# RTC.net
KiCad netlist of a schematic drawn in Altium Designer
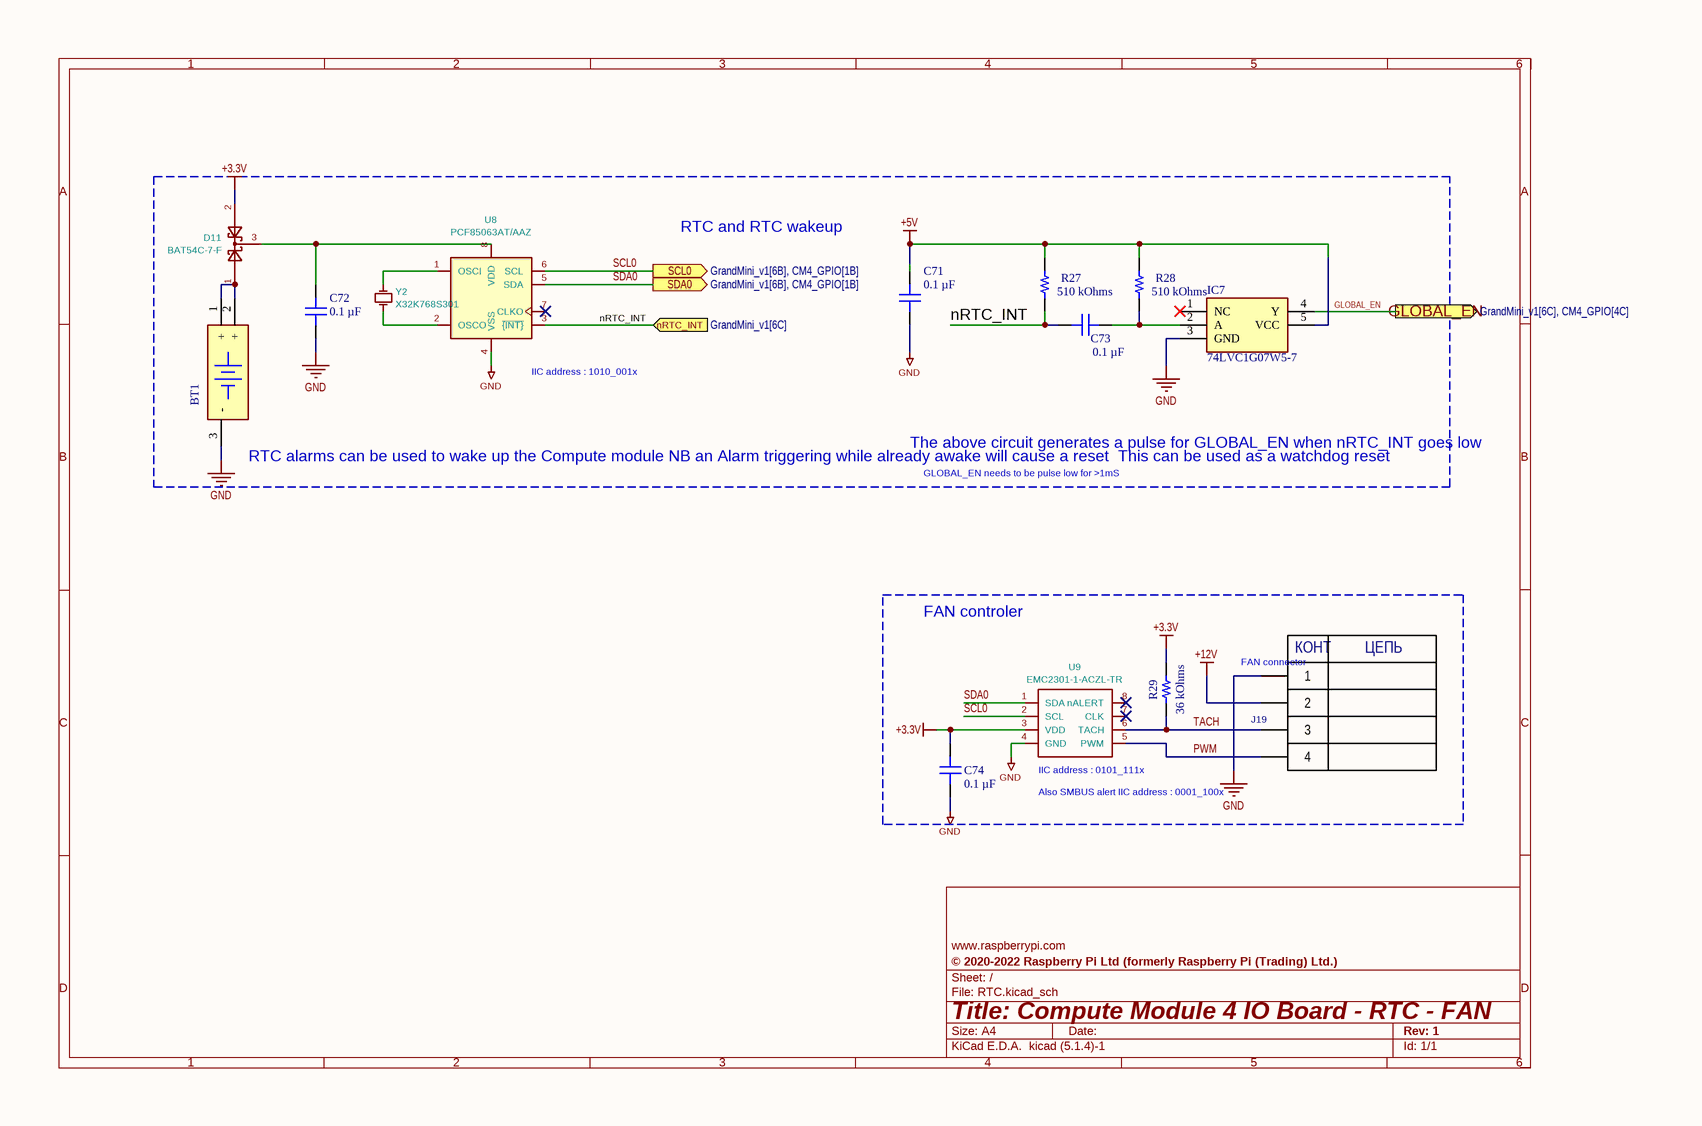
[diagram p0: RTC.SchDoc]

(export (version "E")
  (design (tool "Eeschema 10.0.6"))
  (components
    (comp (ref "BT1")
      (value "CR2032 Holder")
      (footprint "SamacSys:KLS5CR203204")
      (description "Battery Holder, Vertical, CR2032")
      (fields (field (name "MANUFACTURER_PART_NUMBER") "KLS5-CR2032-04"))
      (libsource (lib "SamacSys") (part "KLS5-CR2032-04"))
    )
    (comp (ref "C71")
      (value "0.1 µF")
      (footprint "CAP 0603_1608")
      (description "CAP CER 0.1UF 50V X7R 0603")
      (fields (field (name "PART NUMBER") "CC0603KRX7R9BB104") (field (name "MANUFACTURER") "Yageo"))
      (libsource (lib "Celestial Altium Library - altium_library") (part "Capacitor"))
    )
    (comp (ref "C72")
      (value "0.1 µF")
      (footprint "CAP 0603_1608")
      (description "CAP CER 0.1UF 50V X7R 0603")
      (fields (field (name "PART NUMBER") "CC0603KRX7R9BB104") (field (name "MANUFACTURER") "Yageo"))
      (libsource (lib "Celestial Altium Library - altium_library") (part "Capacitor"))
    )
    (comp (ref "C73")
      (value "0.1 µF")
      (footprint "CAP 0603_1608")
      (description "CAP CER 0.1UF 50V X7R 0603")
      (fields (field (name "PART NUMBER") "CC0603KRX7R9BB104") (field (name "MANUFACTURER") "Yageo"))
      (libsource (lib "Celestial Altium Library - altium_library") (part "Capacitor"))
    )
    (comp (ref "C74")
      (value "0.1 µF")
      (footprint "CAP 0603_1608")
      (description "CAP CER 0.1UF 50V X7R 0603")
      (fields (field (name "PART NUMBER") "CC0603KRX7R9BB104") (field (name "MANUFACTURER") "Yageo"))
      (libsource (lib "Celestial Altium Library - altium_library") (part "Capacitor"))
    )
    (comp (ref "D11") (value "BAT54C-7-F") (footprint "SOT-23") (libsource (lib "Diode") (part "BAT54C")))
    (comp (ref "IC7")
      (value "74LVC1G07W5-7")
      (footprint "SamacSys:SOT95P285X140-5N")
      (description "Integrated Circuit")
      (fields (field (name "MOUSER PART NUMBER") "621-74LVC1G07W5-7"))
      (libsource (lib "SamacSys") (part "74LVC1G07W5-7"))
    )
    (comp (ref "J19")
      (value "WF-4")
      (footprint "SamacSys:WF-4")
      (description "Connector")
      (fields (field (name "MANUFACTURER") "Connfly") (field (name "PART NUMBER") "WF-6"))
      (libsource (lib "SamacSys") (part "WF-4"))
    )
    (comp (ref "R27")
      (value "510 kOhms")
      (footprint "YAGEO RES 0603_1608")
      (description "RES 510K OHM 1% 1/10W 0603")
      (fields (field (name "PART NUMBER") "RC0603FR-07510KL") (field (name "MANUFACTURER") "Yageo"))
      (libsource (lib "Celestial Altium Library - altium_library") (part "Resistor"))
    )
    (comp (ref "R28")
      (value "510 kOhms")
      (footprint "YAGEO RES 0603_1608")
      (description "RES 510K OHM 1% 1/10W 0603")
      (fields (field (name "PART NUMBER") "RC0603FR-07510KL") (field (name "MANUFACTURER") "Yageo"))
      (libsource (lib "Celestial Altium Library - altium_library") (part "Resistor"))
    )
    (comp (ref "R29")
      (value "36 kOhms")
      (footprint "YAGEO RES 0603_1608")
      (description "RES 36K OHM 1% 1/10W 0603")
      (fields (field (name "PART NUMBER") "RC0603FR-0736KL") (field (name "MANUFACTURER") "Yageo"))
      (libsource (lib "Celestial Altium Library - altium_library") (part "Resistor"))
    )
    (comp (ref "U8")
      (value "PCF85063AT/AAZ")
      (footprint "SOIC-8_3.9x4.9mm_P1.27mm")
      (libsource (lib "Timer_RTC") (part "PCF8563T"))
    )
    (comp (ref "U9")
      (value "EMC2301-1-ACZL-TR")
      (footprint "MSOP-8_3x3mm_P0.65mm")
      (libsource (lib "CM4IO") (part "EMC2301"))
    )
    (comp (ref "Y2")
      (value "X32K768S301")
      (footprint "Crystal_SMD_3215-2Pin_3.2x1.5mm")
      (libsource (lib "Device") (part "Crystal_Small"))
    )
  )
  (nets
    (net (code "1") (name "+3.3V") (class "Default")
      (node (ref "C74") (pin "2") (pinfunction "2_2") (pintype "passive"))
      (node (ref "D11") (pin "2") (pinfunction "2_2") (pintype "passive"))
      (node (ref "R29") (pin "1") (pinfunction "1_1") (pintype "passive"))
      (node (ref "U9") (pin "3") (pinfunction "VDD_3") (pintype "passive"))
    )
    (net (code "2") (name "+5V") (class "Default")
      (node (ref "C71") (pin "2") (pinfunction "2_2") (pintype "passive"))
      (node (ref "IC7") (pin "5") (pinfunction "VCC_5") (pintype "passive"))
      (node (ref "R27") (pin "2") (pinfunction "2_2") (pintype "passive"))
      (node (ref "R28") (pin "2") (pinfunction "2_2") (pintype "passive"))
    )
    (net (code "3") (name "+12V") (class "Default")
      (node (ref "J19") (pin "2") (pinfunction "2_2") (pintype "passive"))
    )
    (net (code "4") (name "/GLOBAL_EN") (class "Default")
      (node (ref "IC7") (pin "4") (pinfunction "Y_4") (pintype "passive"))
    )
    (net (code "5") (name "/PWM") (class "Default")
      (node (ref "J19") (pin "4") (pinfunction "4_4") (pintype "passive"))
      (node (ref "U9") (pin "5") (pinfunction "PWM_5") (pintype "passive"))
    )
    (net (code "6") (name "/SCL0") (class "Default")
      (node (ref "U8") (pin "6") (pinfunction "SCL_6") (pintype "passive"))
      (node (ref "U9") (pin "2") (pinfunction "SCL_2") (pintype "passive"))
    )
    (net (code "7") (name "/SDA0") (class "Default")
      (node (ref "U8") (pin "5") (pinfunction "SDA_5") (pintype "passive"))
      (node (ref "U9") (pin "1") (pinfunction "SDA_1") (pintype "passive"))
    )
    (net (code "8") (name "/TACH") (class "Default")
      (node (ref "J19") (pin "3") (pinfunction "3_3") (pintype "passive"))
      (node (ref "R29") (pin "2") (pinfunction "2_2") (pintype "passive"))
      (node (ref "U9") (pin "6") (pinfunction "TACH_6") (pintype "passive"))
    )
    (net (code "9") (name "/nRTC_INT") (class "Default")
      (node (ref "C73") (pin "1") (pinfunction "1_1") (pintype "passive"))
      (node (ref "R27") (pin "1") (pinfunction "1_1") (pintype "passive"))
      (node (ref "U8") (pin "3") (pinfunction "~{{INT}}_3") (pintype "passive"))
    )
    (net (code "10") (name "GND") (class "Default")
      (node (ref "BT1") (pin "3") (pinfunction "-_3") (pintype "passive"))
      (node (ref "C71") (pin "1") (pinfunction "1_1") (pintype "passive"))
      (node (ref "C72") (pin "1") (pinfunction "1_1") (pintype "passive"))
      (node (ref "C74") (pin "1") (pinfunction "1_1") (pintype "passive"))
      (node (ref "IC7") (pin "3") (pinfunction "GND_3") (pintype "passive"))
      (node (ref "J19") (pin "1") (pinfunction "1_1") (pintype "passive"))
      (node (ref "U8") (pin "4") (pinfunction "VSS_4") (pintype "passive"))
      (node (ref "U9") (pin "4") (pinfunction "GND_4") (pintype "passive"))
    )
    (net (code "11") (name "Net-(BT1-+-Pad1)") (class "Default")
      (node (ref "BT1") (pin "1") (pinfunction "+_1") (pintype "passive"))
      (node (ref "BT1") (pin "2") (pinfunction "+_2") (pintype "passive"))
      (node (ref "D11") (pin "1") (pinfunction "1_1") (pintype "passive"))
    )
    (net (code "12") (name "Net-(IC7-A)") (class "Default")
      (node (ref "C73") (pin "2") (pinfunction "2_2") (pintype "passive"))
      (node (ref "IC7") (pin "2") (pinfunction "A_2") (pintype "passive"))
      (node (ref "R28") (pin "1") (pinfunction "1_1") (pintype "passive"))
    )
    (net (code "13") (name "Net-(U8-OSCI)") (class "Default")
      (node (ref "U8") (pin "1") (pinfunction "OSCI_1") (pintype "passive"))
      (node (ref "Y2") (pin "2") (pinfunction "2_2") (pintype "passive"))
    )
    (net (code "14") (name "Net-(U8-OSCO)") (class "Default")
      (node (ref "U8") (pin "2") (pinfunction "OSCO_2") (pintype "passive"))
      (node (ref "Y2") (pin "1") (pinfunction "1_1") (pintype "passive"))
    )
    (net (code "15") (name "Net-(U8-VDD)") (class "Default")
      (node (ref "C72") (pin "2") (pinfunction "2_2") (pintype "passive"))
      (node (ref "D11") (pin "3") (pinfunction "3_3") (pintype "passive"))
      (node (ref "U8") (pin "8") (pinfunction "VDD_8") (pintype "passive"))
    )
    (net (code "16") (name "unconnected-(IC7-NC-Pad1)") (class "Default")
      (node (ref "IC7") (pin "1") (pinfunction "NC_1") (pintype "passive+no_connect"))
    )
    (net (code "17") (name "unconnected-(U8-CLKO-Pad7)") (class "Default")
      (node (ref "U8") (pin "7") (pinfunction "CLKO_7") (pintype "passive+no_connect"))
    )
    (net (code "18") (name "unconnected-(U9-CLK-Pad7)") (class "Default")
      (node (ref "U9") (pin "7") (pinfunction "CLK_7") (pintype "passive+no_connect"))
    )
    (net (code "19") (name "unconnected-(U9-nALERT-Pad8)") (class "Default")
      (node (ref "U9") (pin "8") (pinfunction "nALERT_8") (pintype "passive+no_connect"))
    )
  )
)
